# FT2323_USB_to_Serial.net
KiCad netlist of a schematic drawn in EAGLE
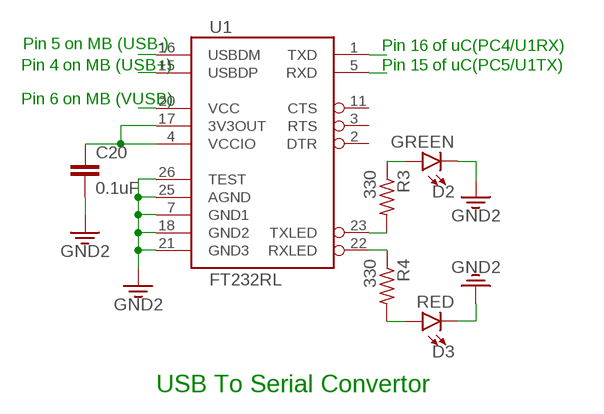
[diagram p0: schematic, sheet 1]

(export (version "E")
  (design (tool "Eeschema 10.0.6"))
  (components
    (comp (ref "C20")
      (value "0.1uF")
      (footprint "eagle-import:1206")
      (libsource (lib "eagle-import") (part "10UF-1206-6.3V-20%"))
    )
    (comp (ref "D2")
      (value "GREEN")
      (footprint "eagle-import:LED-1206")
      (libsource (lib "eagle-import") (part "LED-WHITE1206"))
    )
    (comp (ref "D3")
      (value "RED")
      (footprint "eagle-import:LED-1206")
      (libsource (lib "eagle-import") (part "LED-WHITE1206"))
    )
    (comp (ref "R3")
      (value "330")
      (footprint "eagle-import:M1206")
      (libsource (lib "eagle-import") (part "R-US_M1206"))
    )
    (comp (ref "R4")
      (value "330")
      (footprint "eagle-import:M1206")
      (libsource (lib "eagle-import") (part "R-US_M1206"))
    )
    (comp (ref "U1")
      (value "FT232RL")
      (footprint "eagle-import:SSOP28DB")
      (libsource (lib "eagle-import") (part "FT232RL-BASICSSOP"))
    )
  )
  (nets
    (net (code "1") (name "GND2") (class "Default")
      (node (ref "C20") (pin "2") (pinfunction "2_2") (pintype "passive"))
      (node (ref "D2") (pin "C") (pinfunction "C_C") (pintype "passive"))
      (node (ref "D3") (pin "C") (pinfunction "C_C") (pintype "passive"))
      (node (ref "U1") (pin "18") (pinfunction "GND2_18") (pintype "power_in"))
      (node (ref "U1") (pin "21") (pinfunction "GND3_21") (pintype "power_in"))
      (node (ref "U1") (pin "25") (pinfunction "AGND_25") (pintype "power_in"))
      (node (ref "U1") (pin "26") (pinfunction "TEST_26") (pintype "input"))
      (node (ref "U1") (pin "7") (pinfunction "GND1_7") (pintype "power_in"))
    )
    (net (code "2") (name "Net-(D2-PadA)") (class "Default")
      (node (ref "D2") (pin "A") (pinfunction "A_A") (pintype "passive"))
      (node (ref "R3") (pin "1") (pinfunction "1_1") (pintype "passive"))
    )
    (net (code "3") (name "Net-(D3-PadA)") (class "Default")
      (node (ref "D3") (pin "A") (pinfunction "A_A") (pintype "passive"))
      (node (ref "R4") (pin "2") (pinfunction "2_2") (pintype "passive"))
    )
    (net (code "4") (name "Net-(U1-3V3OUT)") (class "Default")
      (node (ref "C20") (pin "1") (pinfunction "1_1") (pintype "passive"))
      (node (ref "U1") (pin "17") (pinfunction "3V3OUT_17") (pintype "output"))
      (node (ref "U1") (pin "4") (pinfunction "VCCIO_4") (pintype "power_in"))
    )
    (net (code "5") (name "Net-(U1-RXLED)") (class "Default")
      (node (ref "R4") (pin "1") (pinfunction "1_1") (pintype "passive"))
      (node (ref "U1") (pin "22") (pinfunction "RXLED_22") (pintype "bidirectional"))
    )
    (net (code "6") (name "Net-(U1-TXLED)") (class "Default")
      (node (ref "R3") (pin "2") (pinfunction "2_2") (pintype "passive"))
      (node (ref "U1") (pin "23") (pinfunction "TXLED_23") (pintype "bidirectional"))
    )
    (net (code "7") (name "unconnected-(U1-CTS-Pad11)") (class "Default")
      (node (ref "U1") (pin "11") (pinfunction "CTS_11") (pintype "bidirectional"))
    )
    (net (code "8") (name "unconnected-(U1-DTR-Pad2)") (class "Default")
      (node (ref "U1") (pin "2") (pinfunction "DTR_2") (pintype "bidirectional"))
    )
    (net (code "9") (name "unconnected-(U1-RTS-Pad3)") (class "Default")
      (node (ref "U1") (pin "3") (pinfunction "RTS_3") (pintype "bidirectional"))
    )
    (net (code "10") (name "unconnected-(U1-RXD-Pad5)") (class "Default")
      (node (ref "U1") (pin "5") (pinfunction "RXD_5") (pintype "input"))
    )
    (net (code "11") (name "unconnected-(U1-TXD-Pad1)") (class "Default")
      (node (ref "U1") (pin "1") (pinfunction "TXD_1") (pintype "output"))
    )
    (net (code "12") (name "unconnected-(U1-USBDM-Pad16)") (class "Default")
      (node (ref "U1") (pin "16") (pinfunction "USBDM_16") (pintype "bidirectional"))
    )
    (net (code "13") (name "unconnected-(U1-USBDP-Pad15)") (class "Default")
      (node (ref "U1") (pin "15") (pinfunction "USBDP_15") (pintype "bidirectional"))
    )
    (net (code "14") (name "unconnected-(U1-VCC-Pad20)") (class "Default")
      (node (ref "U1") (pin "20") (pinfunction "VCC_20") (pintype "power_in"))
    )
  )
)
